# Gate_Driver.net
KiCad netlist of a schematic drawn in Altium Designer
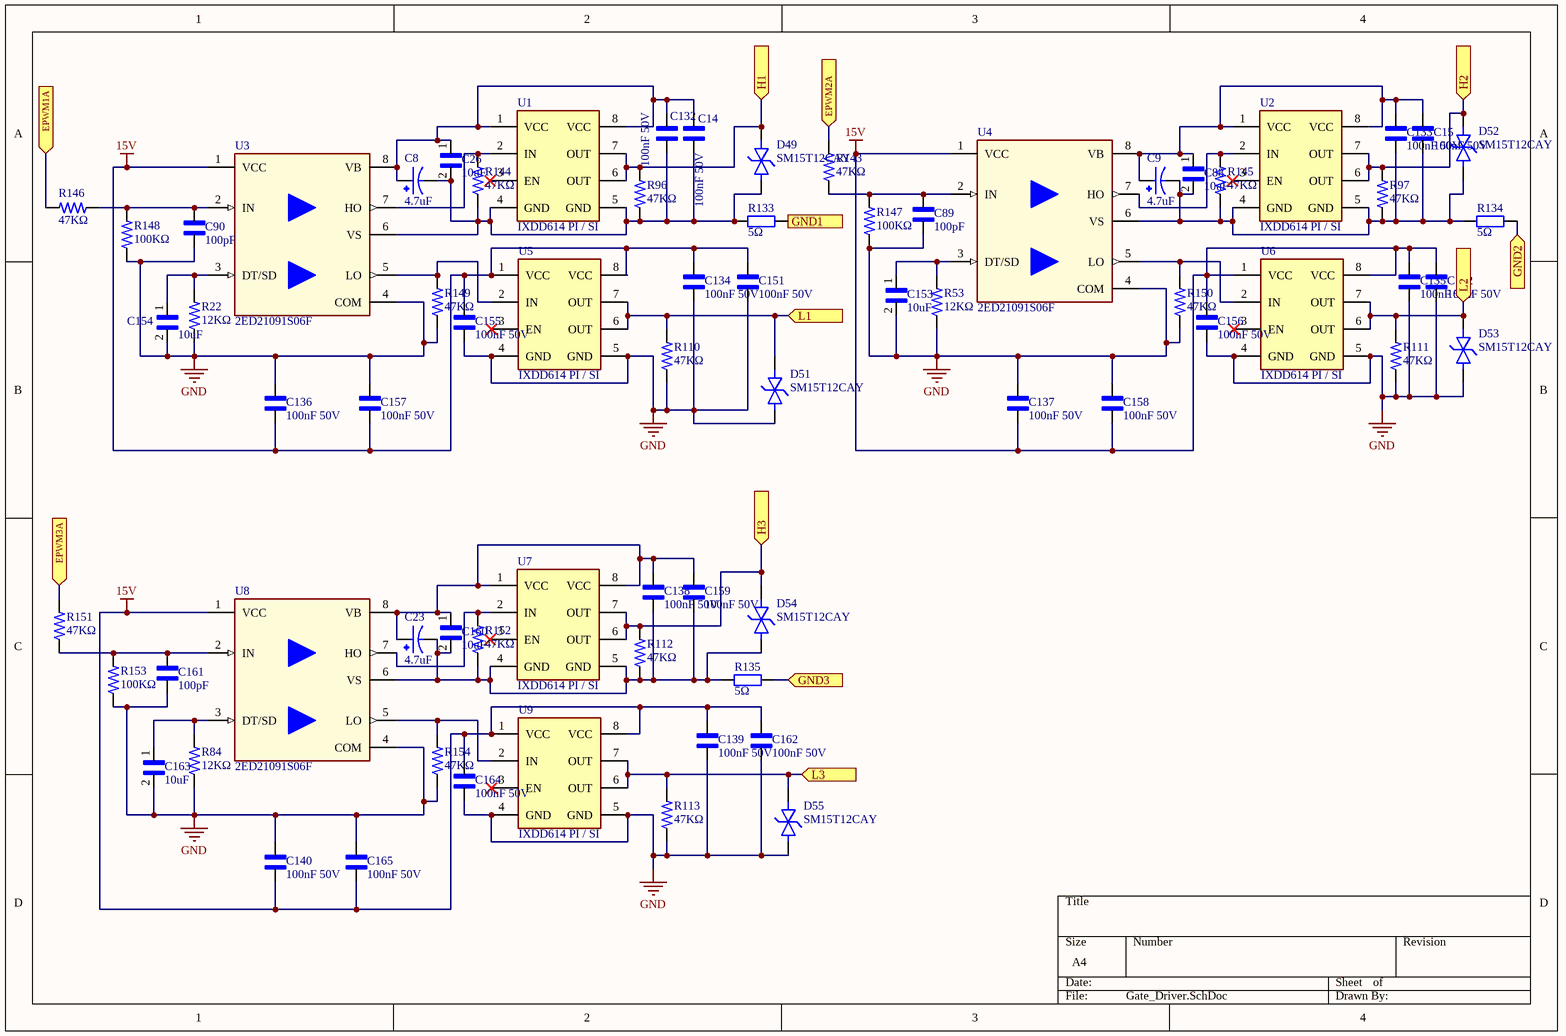
[diagram p0: Gate_Driver.SchDoc]

(export (version "E")
  (design (tool "Eeschema 10.0.6"))
  (components
    (comp (ref "C8")
      (value "4.7uF")
      (footprint "CAP ALSMD POLY 4.3MM H5.5MM")
      (libsource (lib "PROJE") (part "CAP 4.7uF"))
    )
    (comp (ref "C9")
      (value "4.7uF")
      (footprint "CAP ALSMD POLY 4.3MM H5.5MM")
      (libsource (lib "PROJE") (part "CAP 4.7uF"))
    )
    (comp (ref "C14")
      (value "100nF 50V")
      (footprint "C-0805W")
      (fields
        (field (name "MF") "Wurth Electronics Inc")
        (field (name "MP") "885012207098")
        (field (name "BUYPART") "https://www.snapeda.com/parts/885012207098/Wurth%20Electronics%20Inc/view-part/4217223/?ref=eda")
      )
      (libsource (lib "PROJE") (part "CAP 100nF 50V SMT 0805"))
    )
    (comp (ref "C15")
      (value "100nF 50V")
      (footprint "C-0805W")
      (fields
        (field (name "MF") "Wurth Electronics Inc")
        (field (name "MP") "885012207098")
        (field (name "BUYPART") "https://www.snapeda.com/parts/885012207098/Wurth%20Electronics%20Inc/view-part/4217223/?ref=eda")
      )
      (libsource (lib "PROJE") (part "CAP 100nF 50V SMT 0805"))
    )
    (comp (ref "C23")
      (value "4.7uF")
      (footprint "CAP ALSMD POLY 4.3MM H5.5MM")
      (libsource (lib "PROJE") (part "CAP 4.7uF"))
    )
    (comp (ref "C26")
      (value "10uF")
      (footprint "C-0805R")
      (description "0805 10 uF 10 V Â±10% Tolerance X7R Multilayer Ceramic Capacitor")
      (fields (field (name "MP") "GCJ21BR71A106KE01L") (field (name "MF") "Murata"))
      (libsource (lib "PROJE") (part "CAP 10uF 0805 Ceramic"))
    )
    (comp (ref "C88")
      (value "10uF")
      (footprint "C-0805R")
      (description "0805 10 uF 10 V Â±10% Tolerance X7R Multilayer Ceramic Capacitor")
      (fields (field (name "MP") "GCJ21BR71A106KE01L") (field (name "MF") "Murata"))
      (libsource (lib "PROJE") (part "CAP 10uF 0805 Ceramic"))
    )
    (comp (ref "C89") (value "100pF") (footprint "C-0805R") (libsource (lib "PROJE") (part "CAP 100PF 0805")))
    (comp (ref "C90") (value "100pF") (footprint "C-0805R") (libsource (lib "PROJE") (part "CAP 100PF 0805")))
    (comp (ref "C132")
      (value "100nF 50V")
      (footprint "C-0805W")
      (fields
        (field (name "MF") "Wurth Electronics Inc")
        (field (name "MP") "885012207098")
        (field (name "BUYPART") "https://www.snapeda.com/parts/885012207098/Wurth%20Electronics%20Inc/view-part/4217223/?ref=eda")
      )
      (libsource (lib "PROJE") (part "CAP 100nF 50V SMT 0805"))
    )
    (comp (ref "C133")
      (value "100nF 50V")
      (footprint "C-0805W")
      (fields
        (field (name "MF") "Wurth Electronics Inc")
        (field (name "MP") "885012207098")
        (field (name "BUYPART") "https://www.snapeda.com/parts/885012207098/Wurth%20Electronics%20Inc/view-part/4217223/?ref=eda")
      )
      (libsource (lib "PROJE") (part "CAP 100nF 50V SMT 0805"))
    )
    (comp (ref "C134")
      (value "100nF 50V")
      (footprint "C-0805W")
      (fields
        (field (name "MF") "Wurth Electronics Inc")
        (field (name "MP") "885012207098")
        (field (name "BUYPART") "https://www.snapeda.com/parts/885012207098/Wurth%20Electronics%20Inc/view-part/4217223/?ref=eda")
      )
      (libsource (lib "PROJE") (part "CAP 100nF 50V SMT 0805"))
    )
    (comp (ref "C135")
      (value "100nF 50V")
      (footprint "C-0805W")
      (fields
        (field (name "MF") "Wurth Electronics Inc")
        (field (name "MP") "885012207098")
        (field (name "BUYPART") "https://www.snapeda.com/parts/885012207098/Wurth%20Electronics%20Inc/view-part/4217223/?ref=eda")
      )
      (libsource (lib "PROJE") (part "CAP 100nF 50V SMT 0805"))
    )
    (comp (ref "C136")
      (value "100nF 50V")
      (footprint "C-0805W")
      (fields
        (field (name "MF") "Wurth Electronics Inc")
        (field (name "MP") "885012207098")
        (field (name "BUYPART") "https://www.snapeda.com/parts/885012207098/Wurth%20Electronics%20Inc/view-part/4217223/?ref=eda")
      )
      (libsource (lib "PROJE") (part "CAP 100nF 50V SMT 0805"))
    )
    (comp (ref "C137")
      (value "100nF 50V")
      (footprint "C-0805W")
      (fields
        (field (name "MF") "Wurth Electronics Inc")
        (field (name "MP") "885012207098")
        (field (name "BUYPART") "https://www.snapeda.com/parts/885012207098/Wurth%20Electronics%20Inc/view-part/4217223/?ref=eda")
      )
      (libsource (lib "PROJE") (part "CAP 100nF 50V SMT 0805"))
    )
    (comp (ref "C138")
      (value "100nF 50V")
      (footprint "C-0805W")
      (fields
        (field (name "MF") "Wurth Electronics Inc")
        (field (name "MP") "885012207098")
        (field (name "BUYPART") "https://www.snapeda.com/parts/885012207098/Wurth%20Electronics%20Inc/view-part/4217223/?ref=eda")
      )
      (libsource (lib "PROJE") (part "CAP 100nF 50V SMT 0805"))
    )
    (comp (ref "C139")
      (value "100nF 50V")
      (footprint "C-0805W")
      (fields
        (field (name "MF") "Wurth Electronics Inc")
        (field (name "MP") "885012207098")
        (field (name "BUYPART") "https://www.snapeda.com/parts/885012207098/Wurth%20Electronics%20Inc/view-part/4217223/?ref=eda")
      )
      (libsource (lib "PROJE") (part "CAP 100nF 50V SMT 0805"))
    )
    (comp (ref "C140")
      (value "100nF 50V")
      (footprint "C-0805W")
      (fields
        (field (name "MF") "Wurth Electronics Inc")
        (field (name "MP") "885012207098")
        (field (name "BUYPART") "https://www.snapeda.com/parts/885012207098/Wurth%20Electronics%20Inc/view-part/4217223/?ref=eda")
      )
      (libsource (lib "PROJE") (part "CAP 100nF 50V SMT 0805"))
    )
    (comp (ref "C151")
      (value "100nF 50V")
      (footprint "C-0805W")
      (fields
        (field (name "MF") "Wurth Electronics Inc")
        (field (name "MP") "885012207098")
        (field (name "BUYPART") "https://www.snapeda.com/parts/885012207098/Wurth%20Electronics%20Inc/view-part/4217223/?ref=eda")
      )
      (libsource (lib "PROJE") (part "CAP 100nF 50V SMT 0805"))
    )
    (comp (ref "C152")
      (value "100nF 50V")
      (footprint "C-0805W")
      (fields
        (field (name "MF") "Wurth Electronics Inc")
        (field (name "MP") "885012207098")
        (field (name "BUYPART") "https://www.snapeda.com/parts/885012207098/Wurth%20Electronics%20Inc/view-part/4217223/?ref=eda")
      )
      (libsource (lib "PROJE") (part "CAP 100nF 50V SMT 0805"))
    )
    (comp (ref "C153")
      (value "10uF")
      (footprint "C-0805R")
      (description "0805 10 uF 10 V Â±10% Tolerance X7R Multilayer Ceramic Capacitor")
      (fields (field (name "MP") "GCJ21BR71A106KE01L") (field (name "MF") "Murata"))
      (libsource (lib "PROJE") (part "CAP 10uF 0805 Ceramic"))
    )
    (comp (ref "C154")
      (value "10uF")
      (footprint "C-0805R")
      (description "0805 10 uF 10 V Â±10% Tolerance X7R Multilayer Ceramic Capacitor")
      (fields (field (name "MP") "GCJ21BR71A106KE01L") (field (name "MF") "Murata"))
      (libsource (lib "PROJE") (part "CAP 10uF 0805 Ceramic"))
    )
    (comp (ref "C155")
      (value "100nF 50V")
      (footprint "C-0805W")
      (fields
        (field (name "MF") "Wurth Electronics Inc")
        (field (name "MP") "885012207098")
        (field (name "BUYPART") "https://www.snapeda.com/parts/885012207098/Wurth%20Electronics%20Inc/view-part/4217223/?ref=eda")
      )
      (libsource (lib "PROJE") (part "CAP 100nF 50V SMT 0805"))
    )
    (comp (ref "C156")
      (value "100nF 50V")
      (footprint "C-0805W")
      (fields
        (field (name "MF") "Wurth Electronics Inc")
        (field (name "MP") "885012207098")
        (field (name "BUYPART") "https://www.snapeda.com/parts/885012207098/Wurth%20Electronics%20Inc/view-part/4217223/?ref=eda")
      )
      (libsource (lib "PROJE") (part "CAP 100nF 50V SMT 0805"))
    )
    (comp (ref "C157")
      (value "100nF 50V")
      (footprint "C-0805W")
      (fields
        (field (name "MF") "Wurth Electronics Inc")
        (field (name "MP") "885012207098")
        (field (name "BUYPART") "https://www.snapeda.com/parts/885012207098/Wurth%20Electronics%20Inc/view-part/4217223/?ref=eda")
      )
      (libsource (lib "PROJE") (part "CAP 100nF 50V SMT 0805"))
    )
    (comp (ref "C158")
      (value "100nF 50V")
      (footprint "C-0805W")
      (fields
        (field (name "MF") "Wurth Electronics Inc")
        (field (name "MP") "885012207098")
        (field (name "BUYPART") "https://www.snapeda.com/parts/885012207098/Wurth%20Electronics%20Inc/view-part/4217223/?ref=eda")
      )
      (libsource (lib "PROJE") (part "CAP 100nF 50V SMT 0805"))
    )
    (comp (ref "C159")
      (value "100nF 50V")
      (footprint "C-0805W")
      (fields
        (field (name "MF") "Wurth Electronics Inc")
        (field (name "MP") "885012207098")
        (field (name "BUYPART") "https://www.snapeda.com/parts/885012207098/Wurth%20Electronics%20Inc/view-part/4217223/?ref=eda")
      )
      (libsource (lib "PROJE") (part "CAP 100nF 50V SMT 0805"))
    )
    (comp (ref "C160")
      (value "10uF")
      (footprint "C-0805R")
      (description "0805 10 uF 10 V Â±10% Tolerance X7R Multilayer Ceramic Capacitor")
      (fields (field (name "MP") "GCJ21BR71A106KE01L") (field (name "MF") "Murata"))
      (libsource (lib "PROJE") (part "CAP 10uF 0805 Ceramic"))
    )
    (comp (ref "C161")
      (value "100pF")
      (footprint "C-0805R")
      (libsource (lib "PROJE") (part "CAP 100PF 0805"))
    )
    (comp (ref "C162")
      (value "100nF 50V")
      (footprint "C-0805W")
      (fields
        (field (name "MF") "Wurth Electronics Inc")
        (field (name "MP") "885012207098")
        (field (name "BUYPART") "https://www.snapeda.com/parts/885012207098/Wurth%20Electronics%20Inc/view-part/4217223/?ref=eda")
      )
      (libsource (lib "PROJE") (part "CAP 100nF 50V SMT 0805"))
    )
    (comp (ref "C163")
      (value "10uF")
      (footprint "C-0805R")
      (description "0805 10 uF 10 V Â±10% Tolerance X7R Multilayer Ceramic Capacitor")
      (fields (field (name "MP") "GCJ21BR71A106KE01L") (field (name "MF") "Murata"))
      (libsource (lib "PROJE") (part "CAP 10uF 0805 Ceramic"))
    )
    (comp (ref "C164")
      (value "100nF 50V")
      (footprint "C-0805W")
      (fields
        (field (name "MF") "Wurth Electronics Inc")
        (field (name "MP") "885012207098")
        (field (name "BUYPART") "https://www.snapeda.com/parts/885012207098/Wurth%20Electronics%20Inc/view-part/4217223/?ref=eda")
      )
      (libsource (lib "PROJE") (part "CAP 100nF 50V SMT 0805"))
    )
    (comp (ref "C165")
      (value "100nF 50V")
      (footprint "C-0805W")
      (fields
        (field (name "MF") "Wurth Electronics Inc")
        (field (name "MP") "885012207098")
        (field (name "BUYPART") "https://www.snapeda.com/parts/885012207098/Wurth%20Electronics%20Inc/view-part/4217223/?ref=eda")
      )
      (libsource (lib "PROJE") (part "CAP 100nF 50V SMT 0805"))
    )
    (comp (ref "D49")
      (value "SM15T12CAY")
      (footprint "DIOM7959X262N")
      (description "21.7V Clamp 461A (8/20µs) Ipp Tvs Diode Surface Mount SMC")
      (fields (field (name "MP") "SMBJ36CA-13-F") (field (name "MF") "Diodes Inc."))
      (libsource (lib "PROJE") (part "SM15T12CAY"))
    )
    (comp (ref "D51")
      (value "SM15T12CAY")
      (footprint "DIOM7959X262N")
      (description "21.7V Clamp 461A (8/20µs) Ipp Tvs Diode Surface Mount SMC")
      (fields (field (name "MP") "SMBJ36CA-13-F") (field (name "MF") "Diodes Inc."))
      (libsource (lib "PROJE") (part "SM15T12CAY"))
    )
    (comp (ref "D52")
      (value "SM15T12CAY")
      (footprint "DIOM7959X262N")
      (description "21.7V Clamp 461A (8/20µs) Ipp Tvs Diode Surface Mount SMC")
      (fields (field (name "MP") "SMBJ36CA-13-F") (field (name "MF") "Diodes Inc."))
      (libsource (lib "PROJE") (part "SM15T12CAY"))
    )
    (comp (ref "D53")
      (value "SM15T12CAY")
      (footprint "DIOM7959X262N")
      (description "21.7V Clamp 461A (8/20µs) Ipp Tvs Diode Surface Mount SMC")
      (fields (field (name "MP") "SMBJ36CA-13-F") (field (name "MF") "Diodes Inc."))
      (libsource (lib "PROJE") (part "SM15T12CAY"))
    )
    (comp (ref "D54")
      (value "SM15T12CAY")
      (footprint "DIOM7959X262N")
      (description "21.7V Clamp 461A (8/20µs) Ipp Tvs Diode Surface Mount SMC")
      (fields (field (name "MP") "SMBJ36CA-13-F") (field (name "MF") "Diodes Inc."))
      (libsource (lib "PROJE") (part "SM15T12CAY"))
    )
    (comp (ref "D55")
      (value "SM15T12CAY")
      (footprint "DIOM7959X262N")
      (description "21.7V Clamp 461A (8/20µs) Ipp Tvs Diode Surface Mount SMC")
      (fields (field (name "MP") "SMBJ36CA-13-F") (field (name "MF") "Diodes Inc."))
      (libsource (lib "PROJE") (part "SM15T12CAY"))
    )
    (comp (ref "R22")
      (value "12KΩ")
      (footprint "R-1206W")
      (description "Res Thick Film 1206 12K Ohm 1% 0.25W(1/4W) Â±100ppm/Â°C Pad SMD T/R")
      (fields (field (name "MF") "TE Connectivity") (field (name "MP") "1623417-1"))
      (libsource (lib "PROJE") (part "RES 12K 1206"))
    )
    (comp (ref "R53")
      (value "12KΩ")
      (footprint "R-1206W")
      (description "Res Thick Film 1206 12K Ohm 1% 0.25W(1/4W) Â±100ppm/Â°C Pad SMD T/R")
      (fields (field (name "MF") "TE Connectivity") (field (name "MP") "1623417-1"))
      (libsource (lib "PROJE") (part "RES 12K 1206"))
    )
    (comp (ref "R84")
      (value "12KΩ")
      (footprint "R-1206W")
      (description "Res Thick Film 1206 12K Ohm 1% 0.25W(1/4W) Â±100ppm/Â°C Pad SMD T/R")
      (fields (field (name "MF") "TE Connectivity") (field (name "MP") "1623417-1"))
      (libsource (lib "PROJE") (part "RES 12K 1206"))
    )
    (comp (ref "R96")
      (value "47KΩ")
      (footprint "RESC3015X65N")
      (description "47 kOhms ±1% 0.25W, 1/4W Chip Resistor 1206 (3216 Metric) Thick Film")
      (fields (field (name "MP") "CRCW120647K0FKEAC"))
      (libsource (lib "PROJE") (part "RES 47KΩ 1206"))
    )
    (comp (ref "R97")
      (value "47KΩ")
      (footprint "RESC3015X65N")
      (description "47 kOhms ±1% 0.25W, 1/4W Chip Resistor 1206 (3216 Metric) Thick Film")
      (fields (field (name "MP") "CRCW120647K0FKEAC"))
      (libsource (lib "PROJE") (part "RES 47KΩ 1206"))
    )
    (comp (ref "R110")
      (value "47KΩ")
      (footprint "RESC3015X65N")
      (description "47 kOhms ±1% 0.25W, 1/4W Chip Resistor 1206 (3216 Metric) Thick Film")
      (fields (field (name "MP") "CRCW120647K0FKEAC"))
      (libsource (lib "PROJE") (part "RES 47KΩ 1206"))
    )
    (comp (ref "R111")
      (value "47KΩ")
      (footprint "RESC3015X65N")
      (description "47 kOhms ±1% 0.25W, 1/4W Chip Resistor 1206 (3216 Metric) Thick Film")
      (fields (field (name "MP") "CRCW120647K0FKEAC"))
      (libsource (lib "PROJE") (part "RES 47KΩ 1206"))
    )
    (comp (ref "R112")
      (value "47KΩ")
      (footprint "RESC3015X65N")
      (description "47 kOhms ±1% 0.25W, 1/4W Chip Resistor 1206 (3216 Metric) Thick Film")
      (fields (field (name "MP") "CRCW120647K0FKEAC"))
      (libsource (lib "PROJE") (part "RES 47KΩ 1206"))
    )
    (comp (ref "R113")
      (value "47KΩ")
      (footprint "RESC3015X65N")
      (description "47 kOhms ±1% 0.25W, 1/4W Chip Resistor 1206 (3216 Metric) Thick Film")
      (fields (field (name "MP") "CRCW120647K0FKEAC"))
      (libsource (lib "PROJE") (part "RES 47KΩ 1206"))
    )
    (comp (ref "R133") (value "5Ω") (footprint "R-1206W") (libsource (lib "PROJE") (part "5Ω 1206")))
    (comp (ref "R134") (value "5Ω") (footprint "R-1206W") (libsource (lib "PROJE") (part "5Ω 1206")))
    (comp (ref "R135") (value "5Ω") (footprint "R-1206W") (libsource (lib "PROJE") (part "5Ω 1206")))
    (comp (ref "R143")
      (value "47KΩ")
      (footprint "RESC3015X65N")
      (description "47 kOhms ±1% 0.25W, 1/4W Chip Resistor 1206 (3216 Metric) Thick Film")
      (fields (field (name "MP") "CRCW120647K0FKEAC"))
      (libsource (lib "PROJE") (part "RES 47KΩ 1206"))
    )
    (comp (ref "R144")
      (value "47KΩ")
      (footprint "RESC3015X65N")
      (description "47 kOhms ±1% 0.25W, 1/4W Chip Resistor 1206 (3216 Metric) Thick Film")
      (fields (field (name "MP") "CRCW120647K0FKEAC"))
      (libsource (lib "PROJE") (part "RES 47KΩ 1206"))
    )
    (comp (ref "R145")
      (value "47KΩ")
      (footprint "RESC3015X65N")
      (description "47 kOhms ±1% 0.25W, 1/4W Chip Resistor 1206 (3216 Metric) Thick Film")
      (fields (field (name "MP") "CRCW120647K0FKEAC"))
      (libsource (lib "PROJE") (part "RES 47KΩ 1206"))
    )
    (comp (ref "R146")
      (value "47KΩ")
      (footprint "RESC3015X65N")
      (description "47 kOhms ±1% 0.25W, 1/4W Chip Resistor 1206 (3216 Metric) Thick Film")
      (fields (field (name "MP") "CRCW120647K0FKEAC"))
      (libsource (lib "PROJE") (part "RES 47KΩ 1206"))
    )
    (comp (ref "R147")
      (value "100KΩ")
      (footprint "R-0805R")
      (libsource (lib "PROJE") (part "RES 100KΩ 0805"))
    )
    (comp (ref "R148")
      (value "100KΩ")
      (footprint "R-0805R")
      (libsource (lib "PROJE") (part "RES 100KΩ 0805"))
    )
    (comp (ref "R149")
      (value "47KΩ")
      (footprint "RESC3015X65N")
      (description "47 kOhms ±1% 0.25W, 1/4W Chip Resistor 1206 (3216 Metric) Thick Film")
      (fields (field (name "MP") "CRCW120647K0FKEAC"))
      (libsource (lib "PROJE") (part "RES 47KΩ 1206"))
    )
    (comp (ref "R150")
      (value "47KΩ")
      (footprint "RESC3015X65N")
      (description "47 kOhms ±1% 0.25W, 1/4W Chip Resistor 1206 (3216 Metric) Thick Film")
      (fields (field (name "MP") "CRCW120647K0FKEAC"))
      (libsource (lib "PROJE") (part "RES 47KΩ 1206"))
    )
    (comp (ref "R151")
      (value "47KΩ")
      (footprint "RESC3015X65N")
      (description "47 kOhms ±1% 0.25W, 1/4W Chip Resistor 1206 (3216 Metric) Thick Film")
      (fields (field (name "MP") "CRCW120647K0FKEAC"))
      (libsource (lib "PROJE") (part "RES 47KΩ 1206"))
    )
    (comp (ref "R152")
      (value "47KΩ")
      (footprint "RESC3015X65N")
      (description "47 kOhms ±1% 0.25W, 1/4W Chip Resistor 1206 (3216 Metric) Thick Film")
      (fields (field (name "MP") "CRCW120647K0FKEAC"))
      (libsource (lib "PROJE") (part "RES 47KΩ 1206"))
    )
    (comp (ref "R153")
      (value "100KΩ")
      (footprint "R-0805R")
      (libsource (lib "PROJE") (part "RES 100KΩ 0805"))
    )
    (comp (ref "R154")
      (value "47KΩ")
      (footprint "RESC3015X65N")
      (description "47 kOhms ±1% 0.25W, 1/4W Chip Resistor 1206 (3216 Metric) Thick Film")
      (fields (field (name "MP") "CRCW120647K0FKEAC"))
      (libsource (lib "PROJE") (part "RES 47KΩ 1206"))
    )
    (comp (ref "U1")
      (value "IXDD614 PI / SI")
      (footprint "SOIC8-IXD_614")
      (libsource (lib "PROJE") (part "IXD_614"))
    )
    (comp (ref "U2")
      (value "IXDD614 PI / SI")
      (footprint "SOIC8-IXD_614")
      (libsource (lib "PROJE") (part "IXD_614"))
    )
    (comp (ref "U3")
      (value "2ED21091S06F")
      (footprint "SOIC127P600X172-8N-1-V")
      (description "650 V half bridge gate driver with integrated bootstrap diode")
      (fields (field (name "MANUFACTURER") "Infineon Technologies"))
      (libsource (lib "PROJE") (part "2ED21091S06F"))
    )
    (comp (ref "U4")
      (value "2ED21091S06F")
      (footprint "SOIC127P600X172-8N-1-V")
      (description "650 V half bridge gate driver with integrated bootstrap diode")
      (fields (field (name "MANUFACTURER") "Infineon Technologies"))
      (libsource (lib "PROJE") (part "2ED21091S06F"))
    )
    (comp (ref "U5")
      (value "IXDD614 PI / SI")
      (footprint "SOIC8-IXD_614")
      (libsource (lib "PROJE") (part "IXD_614"))
    )
    (comp (ref "U6")
      (value "IXDD614 PI / SI")
      (footprint "SOIC8-IXD_614")
      (libsource (lib "PROJE") (part "IXD_614"))
    )
    (comp (ref "U7")
      (value "IXDD614 PI / SI")
      (footprint "SOIC8-IXD_614")
      (libsource (lib "PROJE") (part "IXD_614"))
    )
    (comp (ref "U8")
      (value "2ED21091S06F")
      (footprint "SOIC127P600X172-8N-1-V")
      (description "650 V half bridge gate driver with integrated bootstrap diode")
      (fields (field (name "MANUFACTURER") "Infineon Technologies"))
      (libsource (lib "PROJE") (part "2ED21091S06F"))
    )
    (comp (ref "U9")
      (value "IXDD614 PI / SI")
      (footprint "SOIC8-IXD_614")
      (libsource (lib "PROJE") (part "IXD_614"))
    )
  )
  (nets
    (net (code "1") (name "/EPWM1A") (class "Default")
      (node (ref "R146") (pin "2") (pinfunction "2_2") (pintype "passive"))
    )
    (net (code "2") (name "/EPWM2A") (class "Default")
      (node (ref "R143") (pin "2") (pinfunction "2_2") (pintype "passive"))
    )
    (net (code "3") (name "/EPWM3A") (class "Default")
      (node (ref "R151") (pin "2") (pinfunction "2_2") (pintype "passive"))
    )
    (net (code "4") (name "/GND1") (class "Default")
      (node (ref "R133") (pin "2") (pinfunction "2_2") (pintype "passive"))
    )
    (net (code "5") (name "/GND2") (class "Default")
      (node (ref "R134") (pin "2") (pinfunction "2_2") (pintype "passive"))
    )
    (net (code "6") (name "/GND3") (class "Default")
      (node (ref "R135") (pin "2") (pinfunction "2_2") (pintype "passive"))
    )
    (net (code "7") (name "/H1") (class "Default")
      (node (ref "D49") (pin "2") (pinfunction "2_2") (pintype "passive"))
      (node (ref "R96") (pin "2") (pinfunction "2_2") (pintype "passive"))
      (node (ref "U1") (pin "6") (pinfunction "OUT_6") (pintype "passive"))
      (node (ref "U1") (pin "7") (pinfunction "OUT_7") (pintype "passive"))
    )
    (net (code "8") (name "/H2") (class "Default")
      (node (ref "D52") (pin "2") (pinfunction "2_2") (pintype "passive"))
      (node (ref "R97") (pin "2") (pinfunction "2_2") (pintype "passive"))
      (node (ref "U2") (pin "6") (pinfunction "OUT_6") (pintype "passive"))
      (node (ref "U2") (pin "7") (pinfunction "OUT_7") (pintype "passive"))
    )
    (net (code "9") (name "/H3") (class "Default")
      (node (ref "D54") (pin "2") (pinfunction "2_2") (pintype "passive"))
      (node (ref "R112") (pin "2") (pinfunction "2_2") (pintype "passive"))
      (node (ref "U7") (pin "6") (pinfunction "OUT_6") (pintype "passive"))
      (node (ref "U7") (pin "7") (pinfunction "OUT_7") (pintype "passive"))
    )
    (net (code "10") (name "/L1") (class "Default")
      (node (ref "D51") (pin "2") (pinfunction "2_2") (pintype "passive"))
      (node (ref "R110") (pin "2") (pinfunction "2_2") (pintype "passive"))
      (node (ref "U5") (pin "6") (pinfunction "OUT_6") (pintype "passive"))
      (node (ref "U5") (pin "7") (pinfunction "OUT_7") (pintype "passive"))
    )
    (net (code "11") (name "/L2") (class "Default")
      (node (ref "D53") (pin "2") (pinfunction "2_2") (pintype "passive"))
      (node (ref "R111") (pin "2") (pinfunction "2_2") (pintype "passive"))
      (node (ref "U6") (pin "6") (pinfunction "OUT_6") (pintype "passive"))
      (node (ref "U6") (pin "7") (pinfunction "OUT_7") (pintype "passive"))
    )
    (net (code "12") (name "/L3") (class "Default")
      (node (ref "D55") (pin "2") (pinfunction "2_2") (pintype "passive"))
      (node (ref "R113") (pin "2") (pinfunction "2_2") (pintype "passive"))
      (node (ref "U9") (pin "6") (pinfunction "OUT_6") (pintype "passive"))
      (node (ref "U9") (pin "7") (pinfunction "OUT_7") (pintype "passive"))
    )
    (net (code "13") (name "15V") (class "Default")
      (node (ref "C134") (pin "2") (pinfunction "2_2") (pintype "passive"))
      (node (ref "C135") (pin "2") (pinfunction "2_2") (pintype "passive"))
      (node (ref "C136") (pin "1") (pinfunction "1_1") (pintype "passive"))
      (node (ref "C137") (pin "1") (pinfunction "1_1") (pintype "passive"))
      (node (ref "C139") (pin "2") (pinfunction "2_2") (pintype "passive"))
      (node (ref "C140") (pin "1") (pinfunction "1_1") (pintype "passive"))
      (node (ref "C151") (pin "2") (pinfunction "2_2") (pintype "passive"))
      (node (ref "C152") (pin "2") (pinfunction "2_2") (pintype "passive"))
      (node (ref "C155") (pin "2") (pinfunction "2_2") (pintype "passive"))
      (node (ref "C156") (pin "2") (pinfunction "2_2") (pintype "passive"))
      (node (ref "C157") (pin "1") (pinfunction "1_1") (pintype "passive"))
      (node (ref "C158") (pin "1") (pinfunction "1_1") (pintype "passive"))
      (node (ref "C162") (pin "2") (pinfunction "2_2") (pintype "passive"))
      (node (ref "C164") (pin "2") (pinfunction "2_2") (pintype "passive"))
      (node (ref "C165") (pin "1") (pinfunction "1_1") (pintype "passive"))
      (node (ref "U3") (pin "1") (pinfunction "VCC_1") (pintype "power_in"))
      (node (ref "U4") (pin "1") (pinfunction "VCC_1") (pintype "power_in"))
      (node (ref "U5") (pin "1") (pinfunction "VCC_1") (pintype "passive"))
      (node (ref "U5") (pin "8") (pinfunction "VCC_8") (pintype "passive"))
      (node (ref "U6") (pin "1") (pinfunction "VCC_1") (pintype "passive"))
      (node (ref "U6") (pin "8") (pinfunction "VCC_8") (pintype "passive"))
      (node (ref "U8") (pin "1") (pinfunction "VCC_1") (pintype "power_in"))
      (node (ref "U9") (pin "1") (pinfunction "VCC_1") (pintype "passive"))
      (node (ref "U9") (pin "8") (pinfunction "VCC_8") (pintype "passive"))
    )
    (net (code "14") (name "GND") (class "Default")
      (node (ref "C134") (pin "1") (pinfunction "1_1") (pintype "passive"))
      (node (ref "C135") (pin "1") (pinfunction "1_1") (pintype "passive"))
      (node (ref "C136") (pin "2") (pinfunction "2_2") (pintype "passive"))
      (node (ref "C137") (pin "2") (pinfunction "2_2") (pintype "passive"))
      (node (ref "C139") (pin "1") (pinfunction "1_1") (pintype "passive"))
      (node (ref "C140") (pin "2") (pinfunction "2_2") (pintype "passive"))
      (node (ref "C151") (pin "1") (pinfunction "1_1") (pintype "passive"))
      (node (ref "C152") (pin "1") (pinfunction "1_1") (pintype "passive"))
      (node (ref "C153") (pin "2") (pinfunction "2_2") (pintype "passive"))
      (node (ref "C154") (pin "2") (pinfunction "2_2") (pintype "passive"))
      (node (ref "C155") (pin "1") (pinfunction "1_1") (pintype "passive"))
      (node (ref "C156") (pin "1") (pinfunction "1_1") (pintype "passive"))
      (node (ref "C157") (pin "2") (pinfunction "2_2") (pintype "passive"))
      (node (ref "C158") (pin "2") (pinfunction "2_2") (pintype "passive"))
      (node (ref "C161") (pin "1") (pinfunction "1_1") (pintype "passive"))
      (node (ref "C162") (pin "1") (pinfunction "1_1") (pintype "passive"))
      (node (ref "C163") (pin "2") (pinfunction "2_2") (pintype "passive"))
      (node (ref "C164") (pin "1") (pinfunction "1_1") (pintype "passive"))
      (node (ref "C165") (pin "2") (pinfunction "2_2") (pintype "passive"))
      (node (ref "C89") (pin "1") (pinfunction "1_1") (pintype "passive"))
      (node (ref "C90") (pin "1") (pinfunction "1_1") (pintype "passive"))
      (node (ref "D51") (pin "1") (pinfunction "1_1") (pintype "passive"))
      (node (ref "D53") (pin "1") (pinfunction "1_1") (pintype "passive"))
      (node (ref "D55") (pin "1") (pinfunction "1_1") (pintype "passive"))
      (node (ref "R110") (pin "1") (pinfunction "1_1") (pintype "passive"))
      (node (ref "R111") (pin "1") (pinfunction "1_1") (pintype "passive"))
      (node (ref "R113") (pin "1") (pinfunction "1_1") (pintype "passive"))
      (node (ref "R147") (pin "1") (pinfunction "1_1") (pintype "passive"))
      (node (ref "R148") (pin "1") (pinfunction "1_1") (pintype "passive"))
      (node (ref "R149") (pin "1") (pinfunction "1_1") (pintype "passive"))
      (node (ref "R150") (pin "1") (pinfunction "1_1") (pintype "passive"))
      (node (ref "R153") (pin "1") (pinfunction "1_1") (pintype "passive"))
      (node (ref "R154") (pin "1") (pinfunction "1_1") (pintype "passive"))
      (node (ref "R22") (pin "1") (pinfunction "1_1") (pintype "passive"))
      (node (ref "R53") (pin "1") (pinfunction "1_1") (pintype "passive"))
      (node (ref "R84") (pin "1") (pinfunction "1_1") (pintype "passive"))
      (node (ref "U3") (pin "4") (pinfunction "COM_4") (pintype "power_in"))
      (node (ref "U4") (pin "4") (pinfunction "COM_4") (pintype "power_in"))
      (node (ref "U5") (pin "4") (pinfunction "GND_4") (pintype "passive"))
      (node (ref "U5") (pin "5") (pinfunction "GND_5") (pintype "passive"))
      (node (ref "U6") (pin "4") (pinfunction "GND_4") (pintype "passive"))
      (node (ref "U6") (pin "5") (pinfunction "GND_5") (pintype "passive"))
      (node (ref "U8") (pin "4") (pinfunction "COM_4") (pintype "power_in"))
      (node (ref "U9") (pin "4") (pinfunction "GND_4") (pintype "passive"))
      (node (ref "U9") (pin "5") (pinfunction "GND_5") (pintype "passive"))
    )
    (net (code "15") (name "Net-(U1-IN)") (class "Default")
      (node (ref "R144") (pin "2") (pinfunction "2_2") (pintype "passive"))
      (node (ref "U1") (pin "2") (pinfunction "IN_2") (pintype "passive"))
      (node (ref "U3") (pin "7") (pinfunction "HO_7") (pintype "output"))
    )
    (net (code "16") (name "Net-(U2-IN)") (class "Default")
      (node (ref "R145") (pin "2") (pinfunction "2_2") (pintype "passive"))
      (node (ref "U2") (pin "2") (pinfunction "IN_2") (pintype "passive"))
      (node (ref "U4") (pin "7") (pinfunction "HO_7") (pintype "output"))
    )
    (net (code "17") (name "Net-(U3-DT{slash}SD)") (class "Default")
      (node (ref "C154") (pin "1") (pinfunction "1_1") (pintype "passive"))
      (node (ref "R22") (pin "2") (pinfunction "2_2") (pintype "passive"))
      (node (ref "U3") (pin "3") (pinfunction "DT/SD_3") (pintype "input"))
    )
    (net (code "18") (name "Net-(U3-IN)") (class "Default")
      (node (ref "C90") (pin "2") (pinfunction "2_2") (pintype "passive"))
      (node (ref "R146") (pin "1") (pinfunction "1_1") (pintype "passive"))
      (node (ref "R148") (pin "2") (pinfunction "2_2") (pintype "passive"))
      (node (ref "U3") (pin "2") (pinfunction "IN_2") (pintype "input"))
    )
    (net (code "19") (name "Net-(U3-LO)") (class "Default")
      (node (ref "R149") (pin "2") (pinfunction "2_2") (pintype "passive"))
      (node (ref "U3") (pin "5") (pinfunction "LO_5") (pintype "output"))
      (node (ref "U5") (pin "2") (pinfunction "IN_2") (pintype "passive"))
    )
    (net (code "20") (name "Net-(U3-VB)") (class "Default")
      (node (ref "C132") (pin "2") (pinfunction "2_2") (pintype "passive"))
      (node (ref "C14") (pin "2") (pinfunction "2_2") (pintype "passive"))
      (node (ref "C26") (pin "1") (pinfunction "1_1") (pintype "passive"))
      (node (ref "C8") (pin "1") (pinfunction "1_1") (pintype "passive"))
      (node (ref "U1") (pin "1") (pinfunction "VCC_1") (pintype "passive"))
      (node (ref "U1") (pin "8") (pinfunction "VCC_8") (pintype "passive"))
      (node (ref "U3") (pin "8") (pinfunction "VB_8") (pintype "power_in"))
    )
    (net (code "21") (name "Net-(U3-VS)") (class "Default")
      (node (ref "C132") (pin "1") (pinfunction "1_1") (pintype "passive"))
      (node (ref "C14") (pin "1") (pinfunction "1_1") (pintype "passive"))
      (node (ref "C26") (pin "2") (pinfunction "2_2") (pintype "passive"))
      (node (ref "C8") (pin "2") (pinfunction "2_2") (pintype "passive"))
      (node (ref "D49") (pin "1") (pinfunction "1_1") (pintype "passive"))
      (node (ref "R133") (pin "1") (pinfunction "1_1") (pintype "passive"))
      (node (ref "R144") (pin "1") (pinfunction "1_1") (pintype "passive"))
      (node (ref "R96") (pin "1") (pinfunction "1_1") (pintype "passive"))
      (node (ref "U1") (pin "4") (pinfunction "GND_4") (pintype "passive"))
      (node (ref "U1") (pin "5") (pinfunction "GND_5") (pintype "passive"))
      (node (ref "U3") (pin "6") (pinfunction "VS_6") (pintype "power_in"))
    )
    (net (code "22") (name "Net-(U4-DT{slash}SD)") (class "Default")
      (node (ref "C153") (pin "1") (pinfunction "1_1") (pintype "passive"))
      (node (ref "R53") (pin "2") (pinfunction "2_2") (pintype "passive"))
      (node (ref "U4") (pin "3") (pinfunction "DT/SD_3") (pintype "input"))
    )
    (net (code "23") (name "Net-(U4-IN)") (class "Default")
      (node (ref "C89") (pin "2") (pinfunction "2_2") (pintype "passive"))
      (node (ref "R143") (pin "1") (pinfunction "1_1") (pintype "passive"))
      (node (ref "R147") (pin "2") (pinfunction "2_2") (pintype "passive"))
      (node (ref "U4") (pin "2") (pinfunction "IN_2") (pintype "input"))
    )
    (net (code "24") (name "Net-(U4-LO)") (class "Default")
      (node (ref "R150") (pin "2") (pinfunction "2_2") (pintype "passive"))
      (node (ref "U4") (pin "5") (pinfunction "LO_5") (pintype "output"))
      (node (ref "U6") (pin "2") (pinfunction "IN_2") (pintype "passive"))
    )
    (net (code "25") (name "Net-(U4-VB)") (class "Default")
      (node (ref "C133") (pin "2") (pinfunction "2_2") (pintype "passive"))
      (node (ref "C15") (pin "2") (pinfunction "2_2") (pintype "passive"))
      (node (ref "C88") (pin "1") (pinfunction "1_1") (pintype "passive"))
      (node (ref "C9") (pin "1") (pinfunction "1_1") (pintype "passive"))
      (node (ref "U2") (pin "1") (pinfunction "VCC_1") (pintype "passive"))
      (node (ref "U2") (pin "8") (pinfunction "VCC_8") (pintype "passive"))
      (node (ref "U4") (pin "8") (pinfunction "VB_8") (pintype "power_in"))
    )
    (net (code "26") (name "Net-(U4-VS)") (class "Default")
      (node (ref "C133") (pin "1") (pinfunction "1_1") (pintype "passive"))
      (node (ref "C15") (pin "1") (pinfunction "1_1") (pintype "passive"))
      (node (ref "C88") (pin "2") (pinfunction "2_2") (pintype "passive"))
      (node (ref "C9") (pin "2") (pinfunction "2_2") (pintype "passive"))
      (node (ref "D52") (pin "1") (pinfunction "1_1") (pintype "passive"))
      (node (ref "R134") (pin "1") (pinfunction "1_1") (pintype "passive"))
      (node (ref "R145") (pin "1") (pinfunction "1_1") (pintype "passive"))
      (node (ref "R97") (pin "1") (pinfunction "1_1") (pintype "passive"))
      (node (ref "U2") (pin "4") (pinfunction "GND_4") (pintype "passive"))
      (node (ref "U2") (pin "5") (pinfunction "GND_5") (pintype "passive"))
      (node (ref "U4") (pin "6") (pinfunction "VS_6") (pintype "power_in"))
    )
    (net (code "27") (name "Net-(U7-IN)") (class "Default")
      (node (ref "R152") (pin "2") (pinfunction "2_2") (pintype "passive"))
      (node (ref "U7") (pin "2") (pinfunction "IN_2") (pintype "passive"))
      (node (ref "U8") (pin "7") (pinfunction "HO_7") (pintype "output"))
    )
    (net (code "28") (name "Net-(U8-DT{slash}SD)") (class "Default")
      (node (ref "C163") (pin "1") (pinfunction "1_1") (pintype "passive"))
      (node (ref "R84") (pin "2") (pinfunction "2_2") (pintype "passive"))
      (node (ref "U8") (pin "3") (pinfunction "DT/SD_3") (pintype "input"))
    )
    (net (code "29") (name "Net-(U8-IN)") (class "Default")
      (node (ref "C161") (pin "2") (pinfunction "2_2") (pintype "passive"))
      (node (ref "R151") (pin "1") (pinfunction "1_1") (pintype "passive"))
      (node (ref "R153") (pin "2") (pinfunction "2_2") (pintype "passive"))
      (node (ref "U8") (pin "2") (pinfunction "IN_2") (pintype "input"))
    )
    (net (code "30") (name "Net-(U8-LO)") (class "Default")
      (node (ref "R154") (pin "2") (pinfunction "2_2") (pintype "passive"))
      (node (ref "U8") (pin "5") (pinfunction "LO_5") (pintype "output"))
      (node (ref "U9") (pin "2") (pinfunction "IN_2") (pintype "passive"))
    )
    (net (code "31") (name "Net-(U8-VB)") (class "Default")
      (node (ref "C138") (pin "2") (pinfunction "2_2") (pintype "passive"))
      (node (ref "C159") (pin "2") (pinfunction "2_2") (pintype "passive"))
      (node (ref "C160") (pin "1") (pinfunction "1_1") (pintype "passive"))
      (node (ref "C23") (pin "1") (pinfunction "1_1") (pintype "passive"))
      (node (ref "U7") (pin "1") (pinfunction "VCC_1") (pintype "passive"))
      (node (ref "U7") (pin "8") (pinfunction "VCC_8") (pintype "passive"))
      (node (ref "U8") (pin "8") (pinfunction "VB_8") (pintype "power_in"))
    )
    (net (code "32") (name "Net-(U8-VS)") (class "Default")
      (node (ref "C138") (pin "1") (pinfunction "1_1") (pintype "passive"))
      (node (ref "C159") (pin "1") (pinfunction "1_1") (pintype "passive"))
      (node (ref "C160") (pin "2") (pinfunction "2_2") (pintype "passive"))
      (node (ref "C23") (pin "2") (pinfunction "2_2") (pintype "passive"))
      (node (ref "D54") (pin "1") (pinfunction "1_1") (pintype "passive"))
      (node (ref "R112") (pin "1") (pinfunction "1_1") (pintype "passive"))
      (node (ref "R135") (pin "1") (pinfunction "1_1") (pintype "passive"))
      (node (ref "R152") (pin "1") (pinfunction "1_1") (pintype "passive"))
      (node (ref "U7") (pin "4") (pinfunction "GND_4") (pintype "passive"))
      (node (ref "U7") (pin "5") (pinfunction "GND_5") (pintype "passive"))
      (node (ref "U8") (pin "6") (pinfunction "VS_6") (pintype "power_in"))
    )
    (net (code "33") (name "unconnected-(U1-EN-Pad3)") (class "Default")
      (node (ref "U1") (pin "3") (pinfunction "EN_3") (pintype "passive+no_connect"))
    )
    (net (code "34") (name "unconnected-(U2-EN-Pad3)") (class "Default")
      (node (ref "U2") (pin "3") (pinfunction "EN_3") (pintype "passive+no_connect"))
    )
    (net (code "35") (name "unconnected-(U5-EN-Pad3)") (class "Default")
      (node (ref "U5") (pin "3") (pinfunction "EN_3") (pintype "passive+no_connect"))
    )
    (net (code "36") (name "unconnected-(U6-EN-Pad3)") (class "Default")
      (node (ref "U6") (pin "3") (pinfunction "EN_3") (pintype "passive+no_connect"))
    )
    (net (code "37") (name "unconnected-(U7-EN-Pad3)") (class "Default")
      (node (ref "U7") (pin "3") (pinfunction "EN_3") (pintype "passive+no_connect"))
    )
    (net (code "38") (name "unconnected-(U9-EN-Pad3)") (class "Default")
      (node (ref "U9") (pin "3") (pinfunction "EN_3") (pintype "passive+no_connect"))
    )
  )
)
